# v2_0.net
KiCad netlist of a schematic drawn in Altium Designer
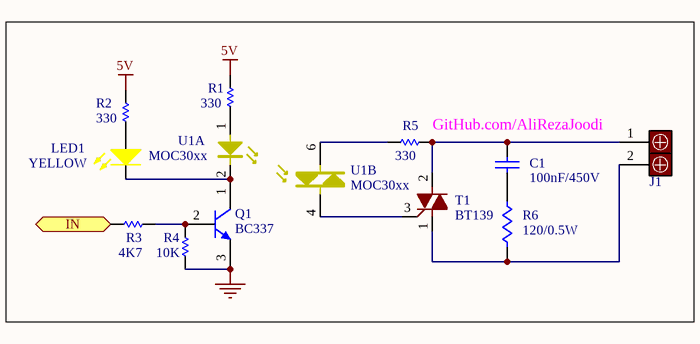
[diagram p0: v2.0.SchDoc]

(export (version "E")
  (design (tool "Eeschema 10.0.6"))
  (components
    (comp (ref "C1")
      (value "100nF/450V")
      (footprint "CAPR7.62-6.8x5")
      (description "Capacitor")
      (fields (field (name "MANUFACTURER") "Generic Components") (field (name "PUBLISHER") "Altium Limited"))
      (libsource (lib "Miscellaneous Devices") (part "Cap"))
    )
    (comp (ref "J1")
      (value "2PIN")
      (footprint "Connector_Phoenix_2PIN_MSTB")
      (description "Connector, Header, 2Pin")
      (libsource (lib "Connector") (part "Connector1x2_Power2"))
    )
    (comp (ref "LED1")
      (value "YELLOW")
      (footprint "LED_THD_3MM_YELLOW_R")
      (description "LED, Yellow")
      (fields (field (name "MANUFACTURER") "Generic Components") (field (name "PUBLISHER") "Altium Limited"))
      (libsource (lib "Display") (part "LED_YELLOW"))
    )
    (comp (ref "Q1")
      (value "BC337")
      (footprint "TO92_3Pin_Form3")
      (description "Transistor, BJT, NPN")
      (libsource (lib "General") (part "Transistor_BJT_NPN"))
    )
    (comp (ref "R1")
      (value "330")
      (footprint "R_THD_AXIAL0.4(1/4W)")
      (description "Resistor")
      (libsource (lib "Passive") (part "Resistor"))
    )
    (comp (ref "R2")
      (value "330")
      (footprint "R_THD_AXIAL0.4(1/4W)")
      (description "Resistor")
      (libsource (lib "Passive") (part "Resistor"))
    )
    (comp (ref "R3")
      (value "4K7")
      (footprint "R_THD_AXIAL0.4(1/4W)")
      (description "Resistor")
      (libsource (lib "Passive") (part "Resistor"))
    )
    (comp (ref "R4")
      (value "10K")
      (footprint "R_THD_AXIAL0.4(1/4W)")
      (description "Resistor")
      (libsource (lib "Passive") (part "Resistor"))
    )
    (comp (ref "R5")
      (value "330")
      (footprint "R_THD_AXIAL0.4(1/4W)")
      (description "Resistor")
      (libsource (lib "Passive") (part "Resistor"))
    )
    (comp (ref "R6")
      (value "120/0.5W")
      (footprint "AXIAL-0.4")
      (description "Resistor")
      (fields (field (name "MANUFACTURER") "Generic Components") (field (name "PUBLISHER") "Altium Limited"))
      (libsource (lib "Miscellaneous Devices") (part "Res1"))
    )
    (comp (ref "T1")
      (value "BT139")
      (footprint "TO220_3PIN_V")
      (description "Triac,")
      (libsource (lib "Passive") (part "Triac"))
    )
    (comp (ref "U1")
      (value "MOC30xx")
      (footprint "DIP_6")
      (description "Opto-Triac")
      (libsource (lib "Other_Myself") (part "MOC3021"))
    )
  )
  (nets
    (net (code "1") (name "/IN") (class "Default")
      (node (ref "R3") (pin "2") (pinfunction "2_2") (pintype "passive"))
    )
    (net (code "2") (name "5V") (class "Default")
      (node (ref "R1") (pin "2") (pinfunction "2_2") (pintype "passive"))
      (node (ref "R2") (pin "2") (pinfunction "2_2") (pintype "passive"))
    )
    (net (code "3") (name "GND") (class "Default")
      (node (ref "Q1") (pin "3") (pinfunction "E_3") (pintype "passive"))
      (node (ref "R4") (pin "2") (pinfunction "2_2") (pintype "passive"))
    )
    (net (code "4") (name "Net-(C1-Pad1)") (class "Default")
      (node (ref "C1") (pin "1") (pinfunction "1_1") (pintype "passive"))
      (node (ref "R6") (pin "2") (pinfunction "2_2") (pintype "passive"))
    )
    (net (code "5") (name "Net-(LED1-A)") (class "Default")
      (node (ref "LED1") (pin "1") (pinfunction "A_1") (pintype "passive"))
      (node (ref "R2") (pin "1") (pinfunction "1_1") (pintype "passive"))
    )
    (net (code "6") (name "Net-(LED1-K)") (class "Default")
      (node (ref "LED1") (pin "2") (pinfunction "K_2") (pintype "passive"))
      (node (ref "Q1") (pin "1") (pinfunction "C_1") (pintype "passive"))
      (node (ref "U1") (pin "2") (pinfunction "K_2") (pintype "power_in"))
    )
    (net (code "7") (name "Net-(Q1-B)") (class "Default")
      (node (ref "Q1") (pin "2") (pinfunction "B_2") (pintype "passive"))
      (node (ref "R3") (pin "1") (pinfunction "1_1") (pintype "passive"))
      (node (ref "R4") (pin "1") (pinfunction "1_1") (pintype "passive"))
    )
    (net (code "8") (name "Net-(R5-Pad1)") (class "Default")
      (node (ref "R5") (pin "1") (pinfunction "1_1") (pintype "passive"))
      (node (ref "U1") (pin "6") (pinfunction "A/K_6") (pintype "passive"))
    )
    (net (code "9") (name "Net-(T1-G)") (class "Default")
      (node (ref "T1") (pin "3") (pinfunction "G_3") (pintype "passive"))
      (node (ref "U1") (pin "4") (pinfunction "A/K_4") (pintype "passive"))
    )
    (net (code "10") (name "Net-(T1-T1)") (class "Default")
      (node (ref "J1") (pin "2") (pinfunction "2_2") (pintype "passive"))
      (node (ref "R6") (pin "1") (pinfunction "1_1") (pintype "passive"))
      (node (ref "T1") (pin "1") (pinfunction "T1_1") (pintype "passive"))
    )
    (net (code "11") (name "Net-(T1-T2)") (class "Default")
      (node (ref "C1") (pin "2") (pinfunction "2_2") (pintype "passive"))
      (node (ref "J1") (pin "1") (pinfunction "1_1") (pintype "passive"))
      (node (ref "R5") (pin "2") (pinfunction "2_2") (pintype "passive"))
      (node (ref "T1") (pin "2") (pinfunction "T2_2") (pintype "passive"))
    )
    (net (code "12") (name "Net-(U1A-A)") (class "Default")
      (node (ref "R1") (pin "1") (pinfunction "1_1") (pintype "passive"))
      (node (ref "U1") (pin "1") (pinfunction "A_1") (pintype "power_in"))
    )
  )
)
